# brakelight_V3.net
KiCad netlist of a schematic drawn in EAGLE
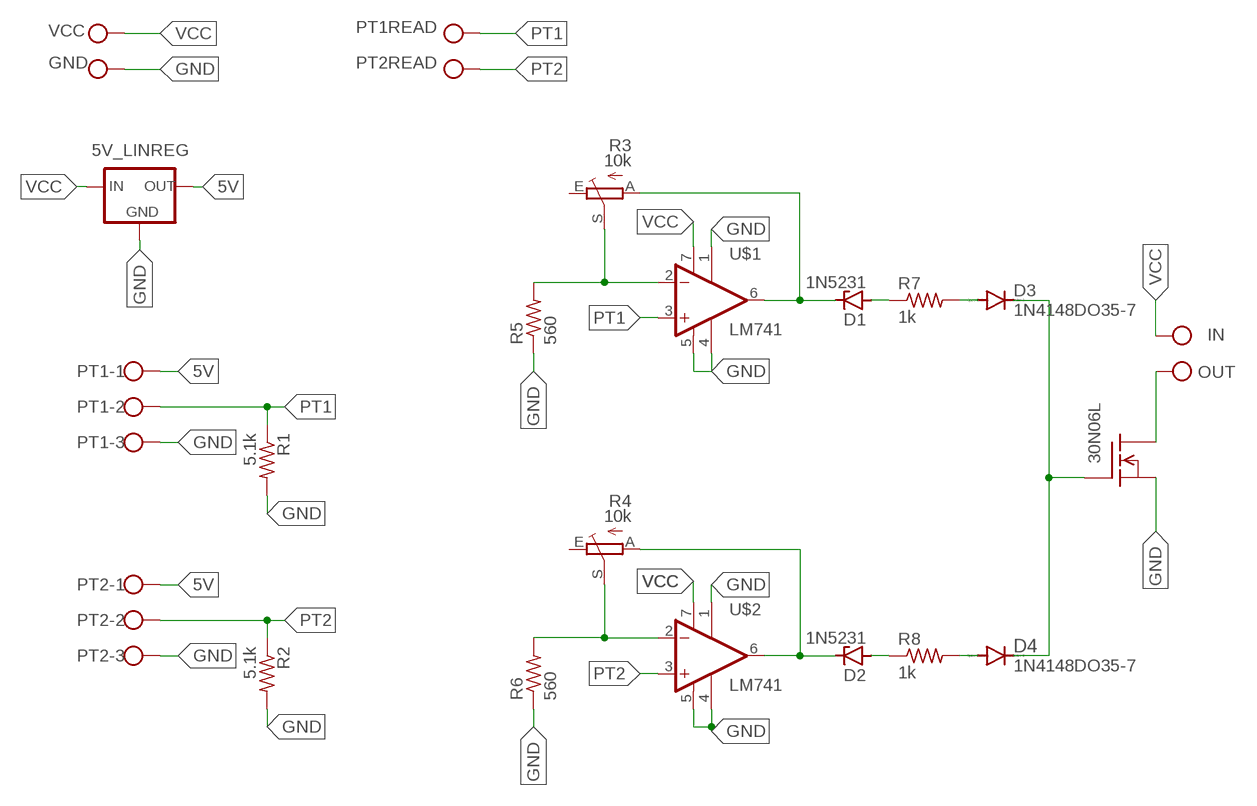
[diagram p0: schematic, sheet 1]

(export (version "E")
  (design (tool "Eeschema 10.0.6"))
  (components
    (comp (ref "5V_LINREG")
      (value "78XXL")
      (footprint "eagle-import:78XXL")
      (libsource (lib "eagle-import") (part "78XXL"))
    )
    (comp (ref "BRAKELIGHT")
      (value "W237-102")
      (footprint "eagle-import:W237-102")
      (fields (field (name "MPN") "237-102"))
      (libsource (lib "eagle-import") (part "W237-102"))
    )
    (comp (ref "D1")
      (value "1N5231")
      (footprint "eagle-import:DO34Z7")
      (libsource (lib "eagle-import") (part "ZENER-DIODEDO34-7"))
    )
    (comp (ref "D2")
      (value "1N5231")
      (footprint "eagle-import:DO34Z7")
      (libsource (lib "eagle-import") (part "ZENER-DIODEDO34-7"))
    )
    (comp (ref "D3")
      (value "1N4148DO35-7")
      (footprint "eagle-import:DO35-7")
      (libsource (lib "eagle-import") (part "1N4148DO35-7"))
    )
    (comp (ref "D4")
      (value "1N4148DO35-7")
      (footprint "eagle-import:DO35-7")
      (libsource (lib "eagle-import") (part "1N4148DO35-7"))
    )
    (comp (ref "INO_READ")
      (value "W237-102")
      (footprint "eagle-import:W237-102")
      (fields (field (name "MPN") "237-102"))
      (libsource (lib "eagle-import") (part "W237-102"))
    )
    (comp (ref "LIPO_CONN")
      (value "W237-102")
      (footprint "eagle-import:W237-102")
      (fields (field (name "MPN") "237-102"))
      (libsource (lib "eagle-import") (part "W237-102"))
    )
    (comp (ref "PT1")
      (value "W237-103")
      (footprint "eagle-import:W237-103")
      (fields (field (name "MPN") "237-103"))
      (libsource (lib "eagle-import") (part "W237-103"))
    )
    (comp (ref "PT2")
      (value "W237-103")
      (footprint "eagle-import:W237-103")
      (fields (field (name "MPN") "237-103"))
      (libsource (lib "eagle-import") (part "W237-103"))
    )
    (comp (ref "Q2")
      (value "30N06L")
      (footprint "eagle-import:TO220")
      (fields (field (name "SPICEPREFIX") "Q"))
      (libsource (lib "eagle-import") (part "SUP75N06-08"))
    )
    (comp (ref "R1")
      (value "5.1k")
      (footprint "eagle-import:0207_5V")
      (libsource (lib "eagle-import") (part "R-US_0207/5V"))
    )
    (comp (ref "R2")
      (value "5.1k")
      (footprint "eagle-import:0207_5V")
      (libsource (lib "eagle-import") (part "R-US_0207/5V"))
    )
    (comp (ref "R3")
      (value "10k")
      (footprint "eagle-import:RS3")
      (libsource (lib "eagle-import") (part "TRIM_EU-RS3"))
    )
    (comp (ref "R4")
      (value "10k")
      (footprint "eagle-import:RS3")
      (libsource (lib "eagle-import") (part "TRIM_EU-RS3"))
    )
    (comp (ref "R5")
      (value "560")
      (footprint "eagle-import:0207_5V")
      (libsource (lib "eagle-import") (part "R-US_0207/5V"))
    )
    (comp (ref "R6")
      (value "560")
      (footprint "eagle-import:0207_5V")
      (libsource (lib "eagle-import") (part "R-US_0207/5V"))
    )
    (comp (ref "R7")
      (value "1k")
      (footprint "eagle-import:0204_5")
      (libsource (lib "eagle-import") (part "R-US_0204/5"))
    )
    (comp (ref "R8")
      (value "1k")
      (footprint "eagle-import:0204_5")
      (libsource (lib "eagle-import") (part "R-US_0204/5"))
    )
    (comp (ref "U$1")
      (value "LM741")
      (footprint "eagle-import:DIL08")
      (libsource (lib "eagle-import") (part "LM741"))
    )
    (comp (ref "U$2")
      (value "LM741")
      (footprint "eagle-import:DIL08")
      (fields (field (name "SPICEPREFIX") "X"))
      (libsource (lib "eagle-import") (part "LM741"))
    )
  )
  (nets
    (net (code "1") (name "5V") (class "Default")
      (node (ref "5V_LINREG") (pin "OUT") (pinfunction "OUT_OUT") (pintype "passive"))
      (node (ref "D1") (pin "C") (pinfunction "C_C") (pintype "passive"))
      (node (ref "PT1") (pin "1") (pinfunction "KL_1") (pintype "passive"))
      (node (ref "PT2") (pin "1") (pinfunction "KL_1") (pintype "passive"))
      (node (ref "R3") (pin "A") (pinfunction "A_A") (pintype "passive"))
      (node (ref "U$1") (pin "6") (pinfunction "OUT_6") (pintype "output"))
    )
    (net (code "2") (name "GND") (class "Default")
      (node (ref "5V_LINREG") (pin "GND") (pinfunction "GND_GND") (pintype "input"))
      (node (ref "LIPO_CONN") (pin "2") (pinfunction "KL_2") (pintype "passive"))
      (node (ref "PT1") (pin "3") (pinfunction "KL_3") (pintype "passive"))
      (node (ref "PT2") (pin "3") (pinfunction "KL_3") (pintype "passive"))
      (node (ref "Q2") (pin "3") (pinfunction "S_3") (pintype "passive"))
      (node (ref "R1") (pin "2") (pinfunction "2_2") (pintype "passive"))
      (node (ref "R2") (pin "2") (pinfunction "2_2") (pintype "passive"))
      (node (ref "R5") (pin "1") (pinfunction "1_1") (pintype "passive"))
      (node (ref "R6") (pin "1") (pinfunction "1_1") (pintype "passive"))
      (node (ref "U$1") (pin "1") (pinfunction "OFFSETNULL_1") (pintype "bidirectional"))
      (node (ref "U$1") (pin "4") (pinfunction "V-_4") (pintype "passive"))
      (node (ref "U$1") (pin "5") (pinfunction "OFFSETNULL2_5") (pintype "bidirectional"))
      (node (ref "U$2") (pin "1") (pinfunction "OFFSETNULL_1") (pintype "bidirectional"))
      (node (ref "U$2") (pin "4") (pinfunction "V-_4") (pintype "passive"))
      (node (ref "U$2") (pin "5") (pinfunction "OFFSETNULL2_5") (pintype "bidirectional"))
    )
    (net (code "3") (name "Net-(BRAKELIGHTB-KL)") (class "Default")
      (node (ref "BRAKELIGHT") (pin "2") (pinfunction "KL_2") (pintype "passive"))
      (node (ref "Q2") (pin "2") (pinfunction "D_2") (pintype "passive"))
    )
    (net (code "4") (name "Net-(D1-PadA)") (class "Default")
      (node (ref "D1") (pin "A") (pinfunction "A_A") (pintype "passive"))
      (node (ref "R7") (pin "1") (pinfunction "1_1") (pintype "passive"))
    )
    (net (code "5") (name "Net-(D2-PadA)") (class "Default")
      (node (ref "D2") (pin "A") (pinfunction "A_A") (pintype "passive"))
      (node (ref "R8") (pin "1") (pinfunction "1_1") (pintype "passive"))
    )
    (net (code "6") (name "Net-(D3-PadA)") (class "Default")
      (node (ref "D3") (pin "A") (pinfunction "A_A") (pintype "passive"))
      (node (ref "R7") (pin "2") (pinfunction "2_2") (pintype "passive"))
    )
    (net (code "7") (name "Net-(D4-PadA)") (class "Default")
      (node (ref "D4") (pin "A") (pinfunction "A_A") (pintype "passive"))
      (node (ref "R8") (pin "2") (pinfunction "2_2") (pintype "passive"))
    )
    (net (code "8") (name "Net-(Q2-G)") (class "Default")
      (node (ref "D3") (pin "C") (pinfunction "C_C") (pintype "passive"))
      (node (ref "D4") (pin "C") (pinfunction "C_C") (pintype "passive"))
      (node (ref "Q2") (pin "1") (pinfunction "G_1") (pintype "passive"))
    )
    (net (code "9") (name "Net-(U$1-INV_INPUT)") (class "Default")
      (node (ref "R3") (pin "S") (pinfunction "S_S") (pintype "passive"))
      (node (ref "R5") (pin "2") (pinfunction "2_2") (pintype "passive"))
      (node (ref "U$1") (pin "2") (pinfunction "INV_INPUT_2") (pintype "input"))
    )
    (net (code "10") (name "Net-(U$2-INV_INPUT)") (class "Default")
      (node (ref "R4") (pin "S") (pinfunction "S_S") (pintype "passive"))
      (node (ref "R6") (pin "2") (pinfunction "2_2") (pintype "passive"))
      (node (ref "U$2") (pin "2") (pinfunction "INV_INPUT_2") (pintype "input"))
    )
    (net (code "11") (name "Net-(U$2-OUT)") (class "Default")
      (node (ref "D2") (pin "C") (pinfunction "C_C") (pintype "passive"))
      (node (ref "R4") (pin "A") (pinfunction "A_A") (pintype "passive"))
      (node (ref "U$2") (pin "6") (pinfunction "OUT_6") (pintype "output"))
    )
    (net (code "12") (name "PT1") (class "Default")
      (node (ref "INO_READ") (pin "1") (pinfunction "KL_1") (pintype "passive"))
      (node (ref "PT1") (pin "2") (pinfunction "KL_2") (pintype "passive"))
      (node (ref "R1") (pin "1") (pinfunction "1_1") (pintype "passive"))
      (node (ref "U$1") (pin "3") (pinfunction "NONINV_INPUT_3") (pintype "input"))
    )
    (net (code "13") (name "PT2") (class "Default")
      (node (ref "INO_READ") (pin "2") (pinfunction "KL_2") (pintype "passive"))
      (node (ref "PT2") (pin "2") (pinfunction "KL_2") (pintype "passive"))
      (node (ref "R2") (pin "1") (pinfunction "1_1") (pintype "passive"))
      (node (ref "U$2") (pin "3") (pinfunction "NONINV_INPUT_3") (pintype "input"))
    )
    (net (code "14") (name "VCC") (class "Default")
      (node (ref "5V_LINREG") (pin "IN") (pinfunction "IN_IN") (pintype "input"))
      (node (ref "BRAKELIGHT") (pin "1") (pinfunction "KL_1") (pintype "passive"))
      (node (ref "LIPO_CONN") (pin "1") (pinfunction "KL_1") (pintype "passive"))
      (node (ref "U$1") (pin "7") (pinfunction "V+_7") (pintype "power_in"))
      (node (ref "U$2") (pin "7") (pinfunction "V+_7") (pintype "power_in"))
    )
    (net (code "15") (name "unconnected-(R3-PadE)") (class "Default")
      (node (ref "R3") (pin "E") (pinfunction "E_E") (pintype "passive"))
    )
    (net (code "16") (name "unconnected-(R4-PadE)") (class "Default")
      (node (ref "R4") (pin "E") (pinfunction "E_E") (pintype "passive"))
    )
  )
)
